# Schematic.net
KiCad netlist of a schematic drawn in Altium Designer
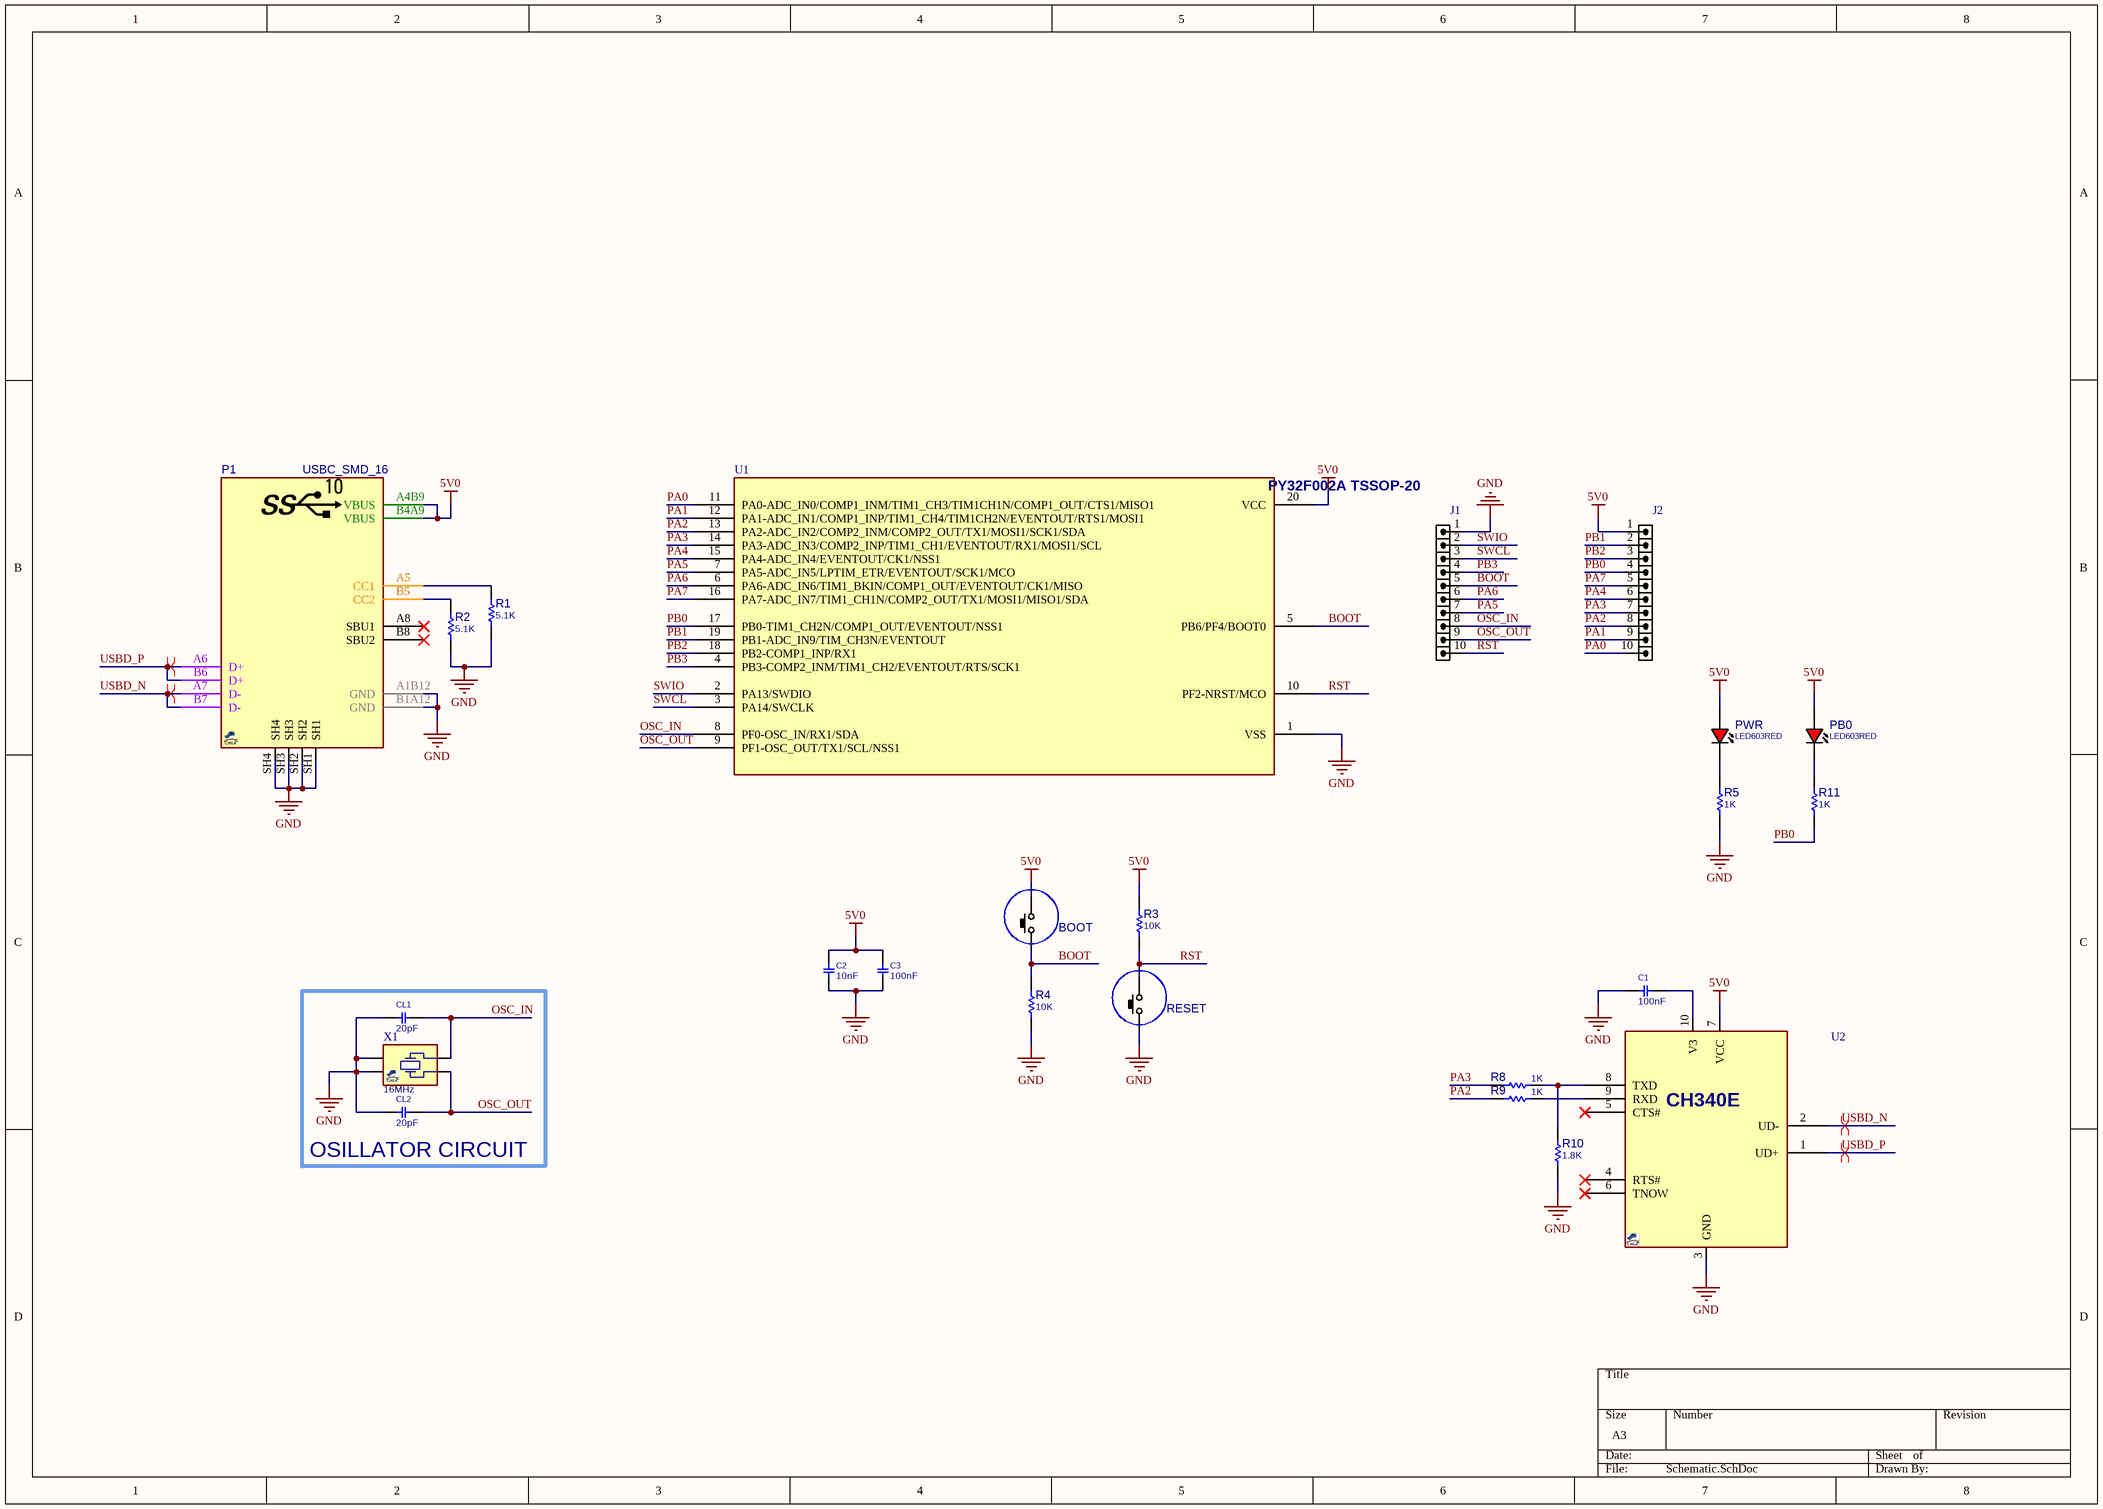
[diagram p0: Schematic.SchDoc]

(export (version "E")
  (design (tool "Eeschema 10.0.6"))
  (components
    (comp (ref "BOOT")
      (value "PUSHBUTTON")
      (footprint "SWPBS_SPST_3X2X1")
      (description "SWITCH, PUSH BUTTON, TACTILE, SMD, SPST, 3X2.5X1.2mm")
      (fields (field (name "MANF") "OMRON") (field (name "MANF_P#") "B3U-1000P"))
      (libsource (lib "switch_tact_PUSHB") (part "SWPBS_SPST_3X2_B3U-1000P"))
    )
    (comp (ref "C1")
      (value "100nF")
      (footprint "C0805")
      (description "CAP, MLCC")
      (fields (field (name "MANF_P#") "MANF_PART#") (field (name "MANF") "Murata"))
      (libsource (lib "passive_smd") (part "CAP_SMD_MLCC"))
    )
    (comp (ref "C2")
      (value "10nF")
      (footprint "C0805")
      (description "CAP, MLCC")
      (fields (field (name "MANF_P#") "MANF_PART#") (field (name "MANF") "Murata"))
      (libsource (lib "passive_smd") (part "CAP_SMD_MLCC"))
    )
    (comp (ref "C3")
      (value "100nF")
      (footprint "C0805")
      (description "CAP, MLCC")
      (fields (field (name "MANF_P#") "MANF_PART#") (field (name "MANF") "Murata"))
      (libsource (lib "passive_smd") (part "CAP_SMD_MLCC"))
    )
    (comp (ref "CL1")
      (value "20pF")
      (footprint "C0805")
      (description "CAP, MLCC")
      (fields (field (name "MANF_P#") "MANF_PART#") (field (name "MANF") "Murata"))
      (libsource (lib "passive_smd") (part "CAP_SMD_MLCC"))
    )
    (comp (ref "CL2")
      (value "20pF")
      (footprint "C0805")
      (description "CAP, MLCC")
      (fields (field (name "MANF_P#") "MANF_PART#") (field (name "MANF") "Murata"))
      (libsource (lib "passive_smd") (part "CAP_SMD_MLCC"))
    )
    (comp (ref "J1")
      (value "HDR1X10")
      (footprint "HDR_M_1X10")
      (description "CONN, HEADER, Male, pitch: 2.54mm, 10POS")
      (libsource (lib "conn_header_2.54mm_st") (part "HDR_M_1X10"))
    )
    (comp (ref "J2")
      (value "HDR1X10")
      (footprint "HDR_M_1X10")
      (description "CONN, HEADER, Male, pitch: 2.54mm, 10POS")
      (libsource (lib "") (part "HDR_M_1X10_1"))
    )
    (comp (ref "P1")
      (value "USBC_SMD_16")
      (footprint "USBC_SMD_16_2171790001")
      (description "CONN, USB, Type C, USB 2.0, Right-Angle, SMD")
      (fields (field (name "MANF") "MOLEX") (field (name "MANF_P#") "2171790001"))
      (libsource (lib "conn_usbc") (part "CONN_USBC_SMD_16_2171790001"))
    )
    (comp (ref "PB0")
      (value "LED603RED")
      (footprint "LED0603RED")
      (description "LED, SMD, 0603, RED")
      (fields (field (name "MANF") "MANF") (field (name "MANF_P#") "MANF_PART#"))
      (libsource (lib "led(diode)") (part "LED_SMD_0603_RED"))
    )
    (comp (ref "PWR")
      (value "LED603RED")
      (footprint "LED0603RED")
      (description "LED, SMD, 0603, RED")
      (fields (field (name "MANF") "MANF") (field (name "MANF_P#") "MANF_PART#"))
      (libsource (lib "led(diode)") (part "LED_SMD_0603_RED"))
    )
    (comp (ref "R1")
      (value "5.1K")
      (footprint "R0603")
      (description "RESISTOR, SMD")
      (libsource (lib "passive_smd") (part "RES_SMD"))
    )
    (comp (ref "R2")
      (value "5.1K")
      (footprint "R0603")
      (description "RESISTOR, SMD")
      (libsource (lib "passive_smd") (part "RES_SMD"))
    )
    (comp (ref "R3")
      (value "10K")
      (footprint "R0603")
      (description "RESISTOR, SMD")
      (libsource (lib "passive_smd") (part "RES_SMD"))
    )
    (comp (ref "R4")
      (value "10K")
      (footprint "R0603")
      (description "RESISTOR, SMD")
      (libsource (lib "passive_smd") (part "RES_SMD"))
    )
    (comp (ref "R5")
      (value "1K")
      (footprint "R0603")
      (description "RESISTOR, SMD")
      (libsource (lib "passive_smd") (part "RES_SMD"))
    )
    (comp (ref "R8")
      (value "1K")
      (footprint "R0603")
      (description "RESISTOR, SMD")
      (libsource (lib "passive_smd") (part "RES_SMD"))
    )
    (comp (ref "R9")
      (value "1K")
      (footprint "R0603")
      (description "RESISTOR, SMD")
      (libsource (lib "passive_smd") (part "RES_SMD"))
    )
    (comp (ref "R10")
      (value "1.8K")
      (footprint "R0603")
      (description "RESISTOR, SMD")
      (libsource (lib "passive_smd") (part "RES_SMD"))
    )
    (comp (ref "R11")
      (value "1K")
      (footprint "R0603")
      (description "RESISTOR, SMD")
      (libsource (lib "passive_smd") (part "RES_SMD"))
    )
    (comp (ref "RESET")
      (value "PUSHBUTTON")
      (footprint "SWPBS_SPST_3X2X1")
      (description "SWITCH, PUSH BUTTON, TACTILE, SMD, SPST, 3X2.5X1.2mm")
      (fields (field (name "MANF") "OMRON") (field (name "MANF_P#") "B3U-1000P"))
      (libsource (lib "switch_tact_PUSHB") (part "SWPBS_SPST_3X2_B3U-1000P"))
    )
    (comp (ref "U1")
      (value "PY32F002A")
      (footprint "SOG65_20")
      (description "MCU, PYUA32 ARM 32-bit, Cortex-M0+, 20KB FLASH, 3KB SRAM")
      (fields (field (name "MANF") "PY") (field (name "MANF_P#") "PY32F002AF15P6TU"))
      (libsource (lib "PY32F002A") (part "PY32F002AF15P6TU_TSSOP20"))
    )
    (comp (ref "U2")
      (value "CH340E")
      (footprint "SOG50_10")
      (description "USB-UART")
      (libsource (lib "usbic") (part "CH340E_MSOP10"))
    )
    (comp (ref "X1")
      (value "16MHz")
      (footprint "XTL_4_2520")
      (description "Crystal 16MHz")
      (fields (field (name "MANF") "ABRACON") (field (name "MANF_P#") "ABM10W-16.0000MHZ-4-D1X-T3"))
      (libsource (lib "crystal") (part "XTL_4_16MHz_2520"))
    )
  )
  (nets
    (net (code "1") (name "/BOOT") (class "Default")
      (node (ref "BOOT") (pin "1") (pinfunction "P1_1") (pintype "passive"))
      (node (ref "J1") (pin "5") (pinfunction "5_5") (pintype "passive"))
      (node (ref "R4") (pin "2") (pinfunction "2_2") (pintype "passive"))
      (node (ref "U1") (pin "5") (pinfunction "PB6/PF4/BOOT0_5") (pintype "passive"))
    )
    (net (code "2") (name "/OSC_IN") (class "Default")
      (node (ref "CL1") (pin "2") (pinfunction "2_2") (pintype "passive"))
      (node (ref "J1") (pin "8") (pinfunction "8_8") (pintype "passive"))
      (node (ref "U1") (pin "8") (pinfunction "PF0-OSC_IN/RX1/SDA_8") (pintype "passive"))
      (node (ref "X1") (pin "1") (pinfunction "1_1") (pintype "passive"))
    )
    (net (code "3") (name "/OSC_OUT") (class "Default")
      (node (ref "CL2") (pin "2") (pinfunction "2_2") (pintype "passive"))
      (node (ref "J1") (pin "9") (pinfunction "9_9") (pintype "passive"))
      (node (ref "U1") (pin "9") (pinfunction "PF1-OSC_OUT/TX1/SCL/NSS1_9") (pintype "passive"))
      (node (ref "X1") (pin "3") (pinfunction "2_3") (pintype "passive"))
    )
    (net (code "4") (name "/PA0") (class "Default")
      (node (ref "J2") (pin "10") (pinfunction "10_10") (pintype "passive"))
      (node (ref "U1") (pin "11") (pinfunction "PA0-ADC_IN0/COMP1_INM/TIM1_CH3/TIM1CH1N/COMP1_OUT/CTS1/MISO1_11") (pintype "passive"))
    )
    (net (code "5") (name "/PA1") (class "Default")
      (node (ref "J2") (pin "9") (pinfunction "9_9") (pintype "passive"))
      (node (ref "U1") (pin "12") (pinfunction "PA1-ADC_IN1/COMP1_INP/TIM1_CH4/TIM1CH2N/EVENTOUT/RTS1/MOSI1_12") (pintype "passive"))
    )
    (net (code "6") (name "/PA2") (class "Default")
      (node (ref "J2") (pin "8") (pinfunction "8_8") (pintype "passive"))
      (node (ref "R9") (pin "2") (pinfunction "2_2") (pintype "passive"))
      (node (ref "U1") (pin "13") (pinfunction "PA2-ADC_IN2/COMP2_INM/COMP2_OUT/TX1/MOSI1/SCK1/SDA_13") (pintype "passive"))
    )
    (net (code "7") (name "/PA3") (class "Default")
      (node (ref "J2") (pin "7") (pinfunction "7_7") (pintype "passive"))
      (node (ref "R8") (pin "2") (pinfunction "2_2") (pintype "passive"))
      (node (ref "U1") (pin "14") (pinfunction "PA3-ADC_IN3/COMP2_INP/TIM1_CH1/EVENTOUT/RX1/MOSI1/SCL_14") (pintype "passive"))
    )
    (net (code "8") (name "/PA4") (class "Default")
      (node (ref "J2") (pin "6") (pinfunction "6_6") (pintype "passive"))
      (node (ref "U1") (pin "15") (pinfunction "PA4-ADC_IN4/EVENTOUT/CK1/NSS1_15") (pintype "passive"))
    )
    (net (code "9") (name "/PA5") (class "Default")
      (node (ref "J1") (pin "7") (pinfunction "7_7") (pintype "passive"))
      (node (ref "U1") (pin "7") (pinfunction "PA5-ADC_IN5/LPTIM_ETR/EVENTOUT/SCK1/MCO_7") (pintype "passive"))
    )
    (net (code "10") (name "/PA6") (class "Default")
      (node (ref "J1") (pin "6") (pinfunction "6_6") (pintype "passive"))
      (node (ref "U1") (pin "6") (pinfunction "PA6-ADC_IN6/TIM1_BKIN/COMP1_OUT/EVENTOUT/CK1/MISO_6") (pintype "passive"))
    )
    (net (code "11") (name "/PA7") (class "Default")
      (node (ref "J2") (pin "5") (pinfunction "5_5") (pintype "passive"))
      (node (ref "U1") (pin "16") (pinfunction "PA7-ADC_IN7/TIM1_CH1N/COMP2_OUT/TX1/MOSI1/MISO1/SDA_16") (pintype "passive"))
    )
    (net (code "12") (name "/PB0") (class "Default")
      (node (ref "J2") (pin "4") (pinfunction "4_4") (pintype "passive"))
      (node (ref "R11") (pin "1") (pinfunction "1_1") (pintype "passive"))
      (node (ref "U1") (pin "17") (pinfunction "PB0-TIM1_CH2N/COMP1_OUT/EVENTOUT/NSS1_17") (pintype "passive"))
    )
    (net (code "13") (name "/PB1") (class "Default")
      (node (ref "J2") (pin "2") (pinfunction "2_2") (pintype "passive"))
      (node (ref "U1") (pin "19") (pinfunction "PB1-ADC_IN9/TIM_CH3N/EVENTOUT_19") (pintype "passive"))
    )
    (net (code "14") (name "/PB2") (class "Default")
      (node (ref "J2") (pin "3") (pinfunction "3_3") (pintype "passive"))
      (node (ref "U1") (pin "18") (pinfunction "PB2-COMP1_INP/RX1_18") (pintype "passive"))
    )
    (net (code "15") (name "/PB3") (class "Default")
      (node (ref "J1") (pin "4") (pinfunction "4_4") (pintype "passive"))
      (node (ref "U1") (pin "4") (pinfunction "PB3-COMP2_INM/TIM1_CH2/EVENTOUT/RTS/SCK1_4") (pintype "passive"))
    )
    (net (code "16") (name "/RST") (class "Default")
      (node (ref "J1") (pin "10") (pinfunction "10_10") (pintype "passive"))
      (node (ref "R3") (pin "1") (pinfunction "1_1") (pintype "passive"))
      (node (ref "RESET") (pin "2") (pinfunction "P3_2") (pintype "passive"))
      (node (ref "U1") (pin "10") (pinfunction "PF2-NRST/MCO_10") (pintype "passive"))
    )
    (net (code "17") (name "/SWCL") (class "Default")
      (node (ref "J1") (pin "3") (pinfunction "3_3") (pintype "passive"))
      (node (ref "U1") (pin "3") (pinfunction "PA14/SWCLK_3") (pintype "passive"))
    )
    (net (code "18") (name "/SWIO") (class "Default")
      (node (ref "J1") (pin "2") (pinfunction "2_2") (pintype "passive"))
      (node (ref "U1") (pin "2") (pinfunction "PA13/SWDIO_2") (pintype "passive"))
    )
    (net (code "19") (name "/USBD_N") (class "Default")
      (node (ref "P1") (pin "A7") (pinfunction "D-_A7") (pintype "passive"))
      (node (ref "P1") (pin "B7") (pinfunction "D-_B7") (pintype "passive"))
      (node (ref "U2") (pin "2") (pinfunction "UD-_2") (pintype "passive"))
    )
    (net (code "20") (name "/USBD_P") (class "Default")
      (node (ref "P1") (pin "A6") (pinfunction "D+_A6") (pintype "passive"))
      (node (ref "P1") (pin "B6") (pinfunction "D+_B6") (pintype "passive"))
      (node (ref "U2") (pin "1") (pinfunction "UD+_1") (pintype "passive"))
    )
    (net (code "21") (name "5V0") (class "Default")
      (node (ref "BOOT") (pin "2") (pinfunction "P3_2") (pintype "passive"))
      (node (ref "C2") (pin "2") (pinfunction "2_2") (pintype "passive"))
      (node (ref "C3") (pin "2") (pinfunction "2_2") (pintype "passive"))
      (node (ref "J2") (pin "1") (pinfunction "1_1") (pintype "passive"))
      (node (ref "P1") (pin "A4B9") (pinfunction "VBUS_A4B9") (pintype "passive"))
      (node (ref "P1") (pin "B4A9") (pinfunction "VBUS_B4A9") (pintype "passive"))
      (node (ref "PB0") (pin "1") (pinfunction "ANODE_1") (pintype "passive"))
      (node (ref "PWR") (pin "1") (pinfunction "ANODE_1") (pintype "passive"))
      (node (ref "R3") (pin "2") (pinfunction "2_2") (pintype "passive"))
      (node (ref "U1") (pin "20") (pinfunction "VCC_20") (pintype "passive"))
      (node (ref "U2") (pin "7") (pinfunction "VCC_7") (pintype "passive"))
    )
    (net (code "22") (name "GND") (class "Default")
      (node (ref "C1") (pin "2") (pinfunction "2_2") (pintype "passive"))
      (node (ref "C2") (pin "1") (pinfunction "1_1") (pintype "passive"))
      (node (ref "C3") (pin "1") (pinfunction "1_1") (pintype "passive"))
      (node (ref "CL1") (pin "1") (pinfunction "1_1") (pintype "passive"))
      (node (ref "CL2") (pin "1") (pinfunction "1_1") (pintype "passive"))
      (node (ref "J1") (pin "1") (pinfunction "1_1") (pintype "passive"))
      (node (ref "P1") (pin "A1B12") (pinfunction "GND_A1B12") (pintype "passive"))
      (node (ref "P1") (pin "B1A12") (pinfunction "GND_B1A12") (pintype "passive"))
      (node (ref "P1") (pin "SH1") (pinfunction "SH1_SH1") (pintype "passive"))
      (node (ref "P1") (pin "SH2") (pinfunction "SH2_SH2") (pintype "passive"))
      (node (ref "P1") (pin "SH3") (pinfunction "SH3_SH3") (pintype "passive"))
      (node (ref "P1") (pin "SH4") (pinfunction "SH4_SH4") (pintype "passive"))
      (node (ref "R1") (pin "1") (pinfunction "1_1") (pintype "passive"))
      (node (ref "R10") (pin "2") (pinfunction "2_2") (pintype "passive"))
      (node (ref "R2") (pin "1") (pinfunction "1_1") (pintype "passive"))
      (node (ref "R4") (pin "1") (pinfunction "1_1") (pintype "passive"))
      (node (ref "R5") (pin "1") (pinfunction "1_1") (pintype "passive"))
      (node (ref "RESET") (pin "1") (pinfunction "P1_1") (pintype "passive"))
      (node (ref "U1") (pin "1") (pinfunction "VSS_1") (pintype "passive"))
      (node (ref "U2") (pin "3") (pinfunction "GND_3") (pintype "passive"))
      (node (ref "X1") (pin "2") (pinfunction "2_2") (pintype "passive"))
      (node (ref "X1") (pin "4") (pinfunction "4_4") (pintype "passive"))
    )
    (net (code "23") (name "Net-(P1-CC1)") (class "Default")
      (node (ref "P1") (pin "A5") (pinfunction "CC1_A5") (pintype "passive"))
      (node (ref "R1") (pin "2") (pinfunction "2_2") (pintype "passive"))
    )
    (net (code "24") (name "Net-(P1-CC2)") (class "Default")
      (node (ref "P1") (pin "B5") (pinfunction "CC2_B5") (pintype "passive"))
      (node (ref "R2") (pin "2") (pinfunction "2_2") (pintype "passive"))
    )
    (net (code "25") (name "Net-(PB0-CATHODE)") (class "Default")
      (node (ref "PB0") (pin "2") (pinfunction "CATHODE_2") (pintype "passive"))
      (node (ref "R11") (pin "2") (pinfunction "2_2") (pintype "passive"))
    )
    (net (code "26") (name "Net-(PWR-CATHODE)") (class "Default")
      (node (ref "PWR") (pin "2") (pinfunction "CATHODE_2") (pintype "passive"))
      (node (ref "R5") (pin "2") (pinfunction "2_2") (pintype "passive"))
    )
    (net (code "27") (name "Net-(U2-RXD)") (class "Default")
      (node (ref "R9") (pin "1") (pinfunction "1_1") (pintype "passive"))
      (node (ref "U2") (pin "9") (pinfunction "RXD_9") (pintype "passive"))
    )
    (net (code "28") (name "Net-(U2-TXD)") (class "Default")
      (node (ref "R10") (pin "1") (pinfunction "1_1") (pintype "passive"))
      (node (ref "R8") (pin "1") (pinfunction "1_1") (pintype "passive"))
      (node (ref "U2") (pin "8") (pinfunction "TXD_8") (pintype "passive"))
    )
    (net (code "29") (name "Net-(U2-V3)") (class "Default")
      (node (ref "C1") (pin "1") (pinfunction "1_1") (pintype "passive"))
      (node (ref "U2") (pin "10") (pinfunction "V3_10") (pintype "passive"))
    )
    (net (code "30") (name "unconnected-(P1-SBU1-PadA8)") (class "Default")
      (node (ref "P1") (pin "A8") (pinfunction "SBU1_A8") (pintype "passive+no_connect"))
    )
    (net (code "31") (name "unconnected-(P1-SBU2-PadB8)") (class "Default")
      (node (ref "P1") (pin "B8") (pinfunction "SBU2_B8") (pintype "passive+no_connect"))
    )
    (net (code "32") (name "unconnected-(U2-CTS#-Pad5)") (class "Default")
      (node (ref "U2") (pin "5") (pinfunction "CTS#_5") (pintype "passive+no_connect"))
    )
    (net (code "33") (name "unconnected-(U2-RTS#-Pad4)") (class "Default")
      (node (ref "U2") (pin "4") (pinfunction "RTS#_4") (pintype "passive+no_connect"))
    )
    (net (code "34") (name "unconnected-(U2-TNOW-Pad6)") (class "Default")
      (node (ref "U2") (pin "6") (pinfunction "TNOW_6") (pintype "passive+no_connect"))
    )
  )
)
